# ProPrj_My_FOC_DRV8313_Share.net
KiCad netlist of a schematic drawn in EasyEDA Pro
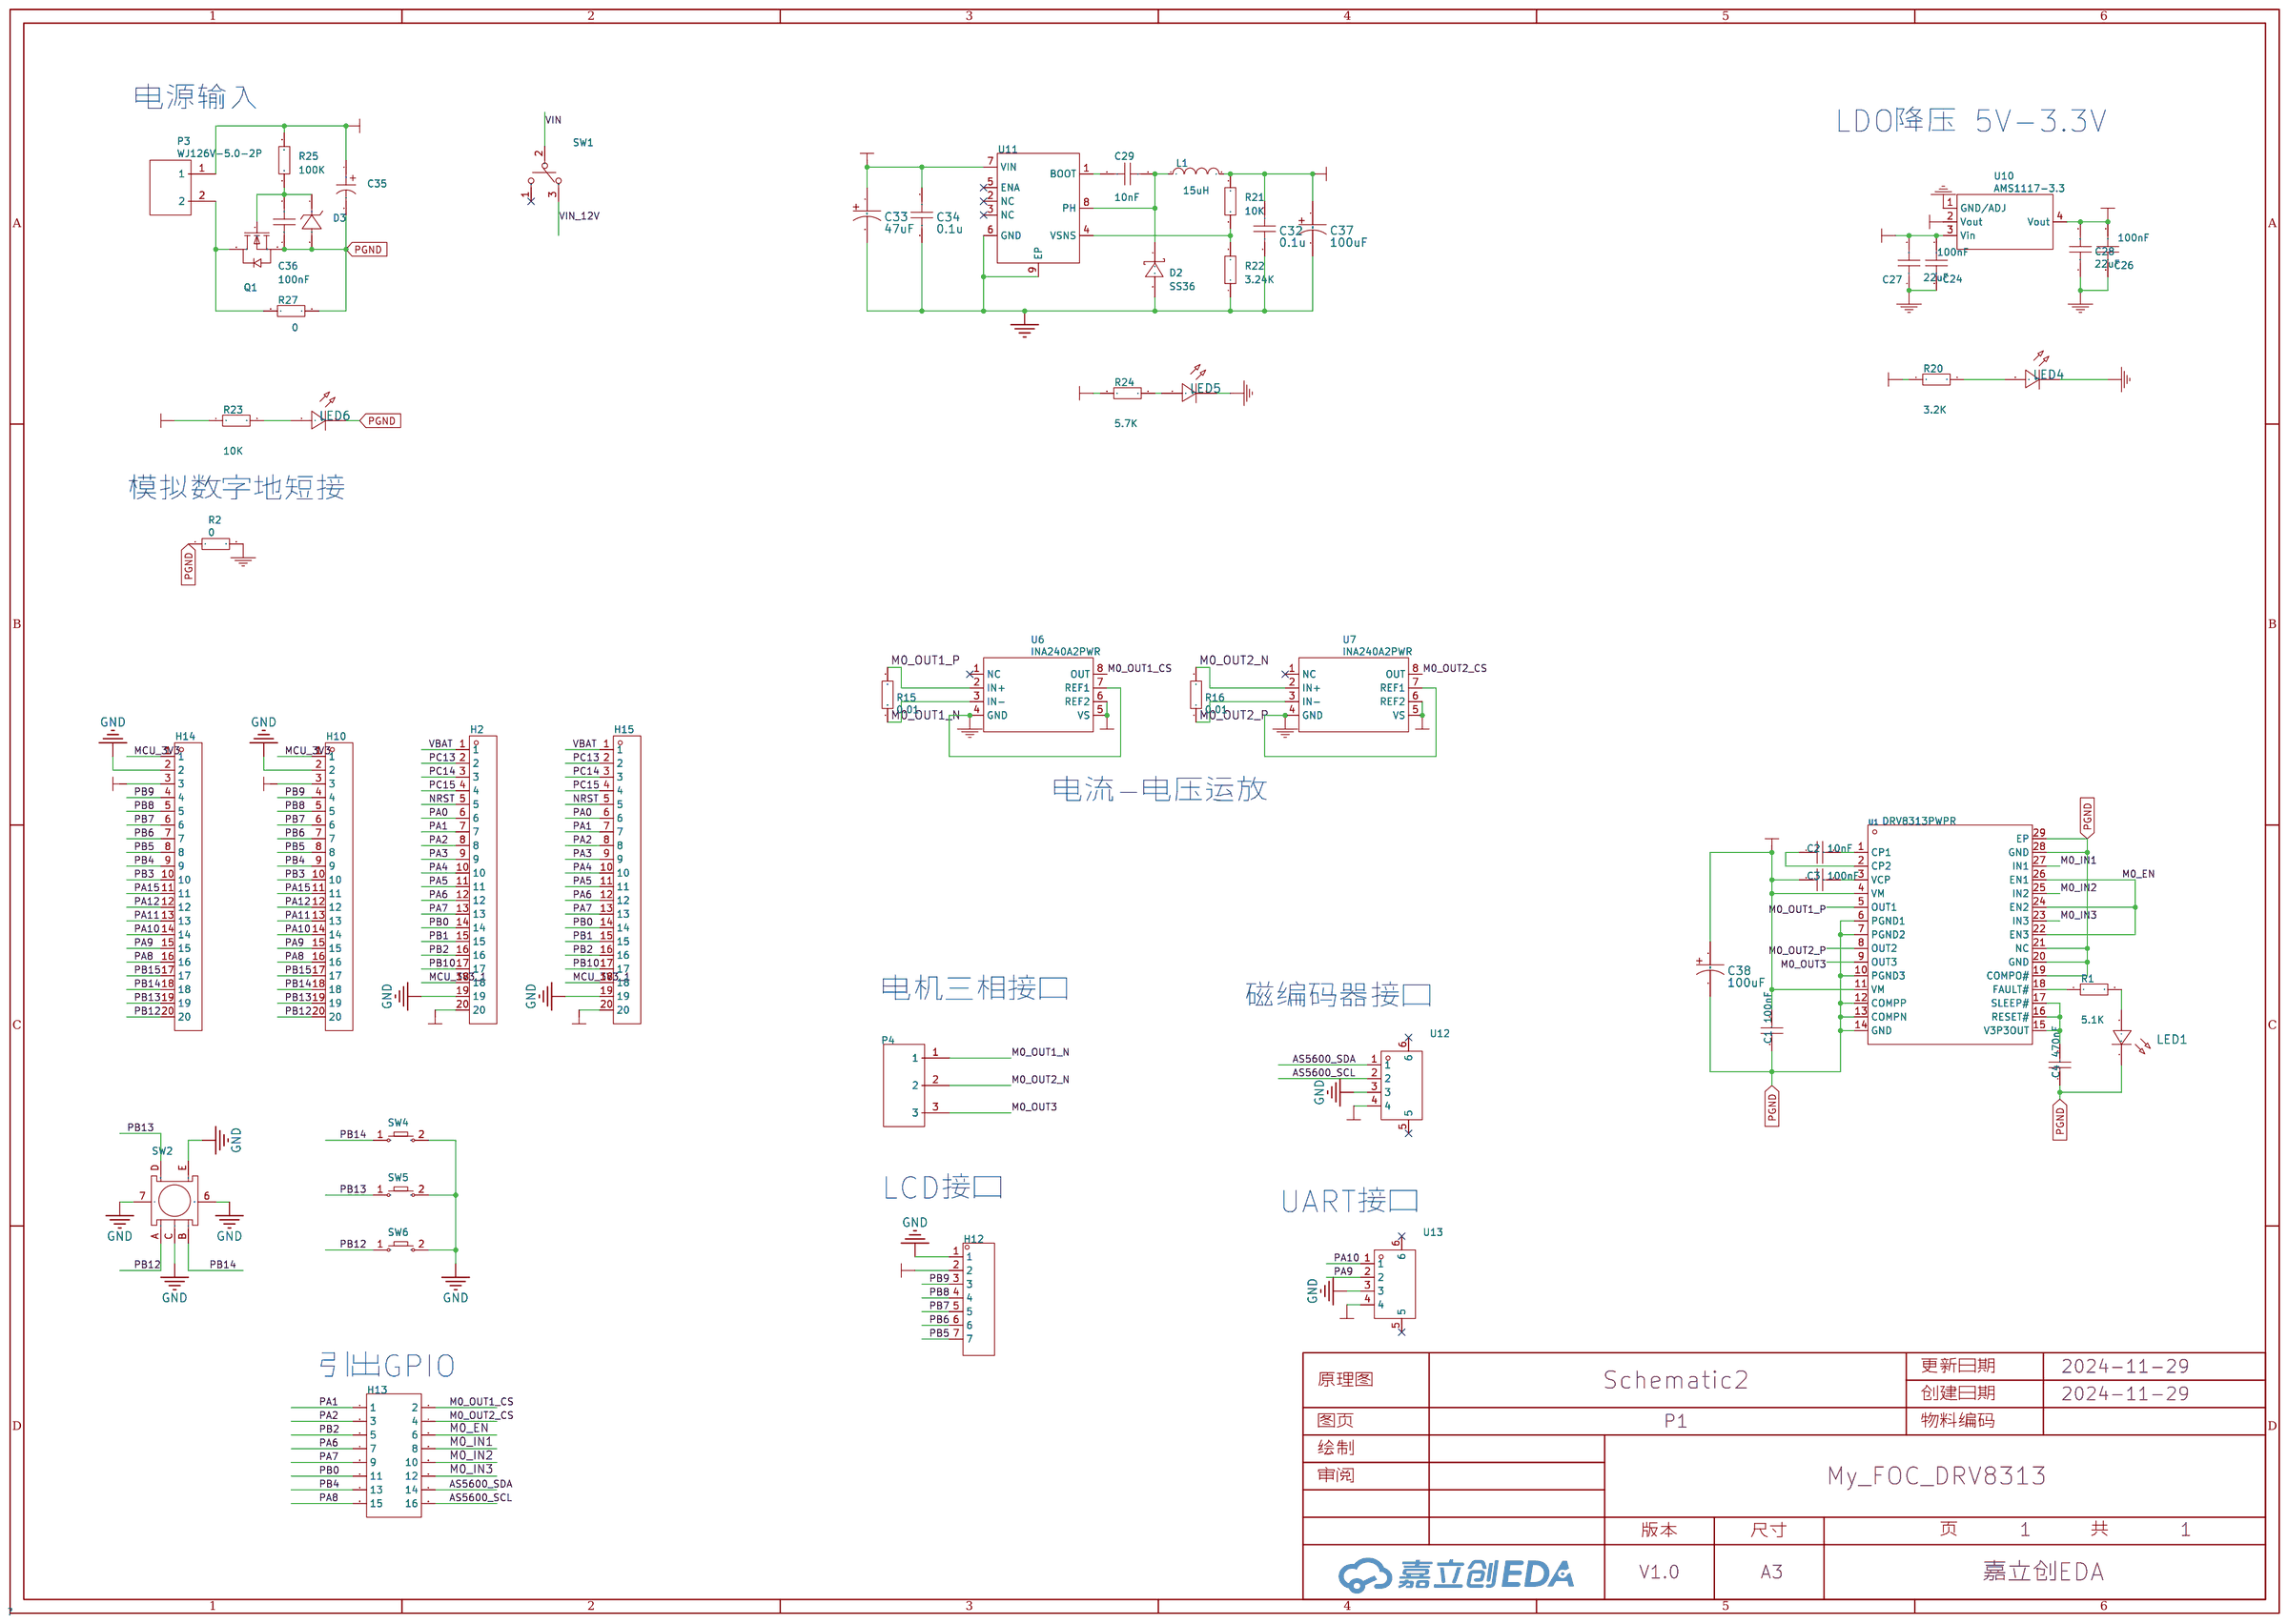
[diagram p0: schematic sheet]

(export (version "E")
  (design (tool "Eeschema 10.0.6"))
  (components
    (comp (ref "C1")
      (value "100nF")
      (footprint "easyedapro:C0603")
      (description "容值:100nF;精度:±10%;额定电压:50V;材质(温度系数):X7R;")
      (fields (field (name "Manufacturer Part") "0603B104K500NT") (field (name "Manufacturer") "FH(风华)"))
      (libsource (lib "easyedapro") (part "0603B104K500NT"))
    )
    (comp (ref "C2")
      (value "10nF")
      (footprint "easyedapro:C0603")
      (description "容值:10nF;精度:±10%;额定电压:50V;材质(温度系数):X7R;")
      (fields
        (field (name "Manufacturer Part") "CC0603KRX7R9BB103")
        (field (name "Manufacturer") "YAGEO(国巨)")
      )
      (libsource (lib "easyedapro") (part "CC0603KRX7R9BB103"))
    )
    (comp (ref "C3")
      (value "100nF")
      (footprint "easyedapro:C0603")
      (description "容值:100nF;精度:±10%;额定电压:50V;材质(温度系数):X7R;")
      (fields (field (name "Manufacturer Part") "0603B104K500NT") (field (name "Manufacturer") "FH(风华)"))
      (libsource (lib "easyedapro") (part "0603B104K500NT"))
    )
    (comp (ref "C4")
      (value "470nF")
      (footprint "easyedapro:C0603")
      (description "容值:470nF;精度:±10%;额定电压:25V;材质(温度系数):X7R;")
      (fields
        (field (name "Manufacturer Part") "CL10B474KA8NNNC")
        (field (name "Manufacturer") "SAMSUNG(三星)")
      )
      (libsource (lib "easyedapro") (part "CL10B474KA8NNNC"))
    )
    (comp (ref "C24")
      (value "100nF")
      (footprint "easyedapro:C0603")
      (fields (field (name "Manufacturer Part") "CC0603KRX7R9BB104") (field (name "Manufacturer") "YAGEO"))
      (libsource (lib "easyedapro") (part "100nF"))
    )
    (comp (ref "C26")
      (value "100nF")
      (footprint "easyedapro:C0603")
      (fields (field (name "Manufacturer Part") "CC0603KRX7R9BB104") (field (name "Manufacturer") "YAGEO"))
      (libsource (lib "easyedapro") (part "100nF"))
    )
    (comp (ref "C27")
      (value "22uF")
      (footprint "easyedapro:C0603")
      (fields (field (name "Manufacturer Part") "CL10A226MQ8NRNC") (field (name "Manufacturer") "SAMSUNG"))
      (libsource (lib "") (part "22uF_1"))
    )
    (comp (ref "C28")
      (value "22uF")
      (footprint "easyedapro:C0603")
      (fields (field (name "Manufacturer Part") "CL10A226MQ8NRNC") (field (name "Manufacturer") "SAMSUNG"))
      (libsource (lib "") (part "22uF_1"))
    )
    (comp (ref "C29")
      (value "10nF")
      (footprint "easyedapro:C0603")
      (libsource (lib "easyedapro") (part "CapAcitance"))
    )
    (comp (ref "C32")
      (value "0.1u")
      (footprint "easyedapro:C0603")
      (libsource (lib "easyedapro") (part "0.1u"))
    )
    (comp (ref "C33")
      (value "47uF")
      (footprint "easyedapro:CAP-SMD_BD5.0-L5.3-W5.3-FD")
      (fields (field (name "Manufacturer Part") "RVE1E220M0505") (field (name "Manufacturer") "HONOR"))
      (libsource (lib "easyedapro") (part "22uF"))
    )
    (comp (ref "C34")
      (value "0.1u")
      (footprint "easyedapro:C0603")
      (libsource (lib "easyedapro") (part "0.1u"))
    )
    (comp (ref "C35")
      (value "LZ1C471M0810")
      (footprint "easyedapro:CAP-SMD_BD8.0-L8.3-W8.3-LS9.3-FD-2")
      (description "容值: 470uF 精度: ±20% 额定电压: 16V 电容直径: 8mm 电容高度: 10.5mm 工作温度: 2000H@105°C贴片型铝电解电容")
      (fields (field (name "Manufacturer") "JARSON(伽盛)"))
      (libsource (lib "easyedapro") (part "LZ1C471M0810"))
    )
    (comp (ref "C36")
      (value "100nF")
      (footprint "easyedapro:C0603")
      (libsource (lib "easyedapro") (part "CapAcitance"))
    )
    (comp (ref "C37")
      (value "100uF")
      (footprint "easyedapro:CAP-SMD_BD5.0-L5.3-W5.3-FD")
      (fields (field (name "Manufacturer Part") "RVE1E220M0505") (field (name "Manufacturer") "HONOR"))
      (libsource (lib "easyedapro") (part "22uF"))
    )
    (comp (ref "C38")
      (value "100uF")
      (footprint "easyedapro:CAP-SMD_BD5.0-L5.3-W5.3-FD")
      (fields (field (name "Manufacturer Part") "RVE1E220M0505") (field (name "Manufacturer") "HONOR"))
      (libsource (lib "easyedapro") (part "22uF"))
    )
    (comp (ref "D2")
      (value "SS36")
      (footprint "easyedapro:SMA_L4.3-W2.6-LS5.2-RD")
      (fields (field (name "Manufacturer") "MDD"))
      (libsource (lib "easyedapro") (part "SS36"))
    )
    (comp (ref "D3")
      (value "ZMM12")
      (footprint "easyedapro:LL-34_L3.5-W1.5-RD")
      (description "稳压值(标称值):-;功率(Pd):500mW;")
      (fields (field (name "Manufacturer") "Slkor(萨科微)"))
      (libsource (lib "easyedapro") (part "ZMM12_C707203"))
    )
    (comp (ref "H2")
      (value "~")
      (footprint "easyedapro:HDR-TH_20P-P2.54-V-M-1")
      (libsource (lib "easyedapro") (part "HDR_2.54-1x20P"))
    )
    (comp (ref "H10")
      (value "~")
      (footprint "easyedapro:HDR-TH_20P-P2.54-V-M-1")
      (libsource (lib "easyedapro") (part "HDR_2.54-1x20P"))
    )
    (comp (ref "H12")
      (value "~")
      (footprint "easyedapro:HDR-TH_7P-P2.54-V-F")
      (libsource (lib "easyedapro") (part "220S-1*7P H=8.5MM Ytype Gold-plated"))
    )
    (comp (ref "H13")
      (value "~")
      (footprint "easyedapro:HDR-TH_16P-P2.54-V-F-R2-C8-S2.54-1")
      (libsource (lib "easyedapro") (part "HDR-F-2.54_2x8"))
    )
    (comp (ref "H14")
      (value "~")
      (footprint "easyedapro:HDR-TH_20P-P2.54-V-M-1")
      (libsource (lib "easyedapro") (part "HDR_2.54-1x20P"))
    )
    (comp (ref "H15")
      (value "~")
      (footprint "easyedapro:HDR-TH_20P-P2.54-V-M-1")
      (libsource (lib "easyedapro") (part "HDR_2.54-1x20P"))
    )
    (comp (ref "L1")
      (value "15uH")
      (footprint "easyedapro:IND-SMD_L4.0-W4.0")
      (description "电感值:10uH;精度:±20%;额定电流:840mA;饱和电流(Isat):1.6A;类型:-;")
      (fields (field (name "Manufacturer Part") "SWPA4018S100MT") (field (name "Manufacturer") "Sunlord(顺络)"))
      (libsource (lib "easyedapro") (part "SWPA4018S100MT"))
    )
    (comp (ref "LED1")
      (value "~")
      (footprint "easyedapro:LED_0603")
      (libsource (lib "easyedapro") (part "LED_R"))
    )
    (comp (ref "LED4")
      (value "~")
      (footprint "easyedapro:LED_0603")
      (libsource (lib "easyedapro") (part "LED_R"))
    )
    (comp (ref "LED5")
      (value "~")
      (footprint "easyedapro:LED_0603")
      (libsource (lib "easyedapro") (part "LED_R"))
    )
    (comp (ref "LED6")
      (value "~")
      (footprint "easyedapro:LED_0603")
      (libsource (lib "easyedapro") (part "LED_R"))
    )
    (comp (ref "P3")
      (value "WJ126V-5.0-2P")
      (footprint "easyedapro:conn-th_wj126v-5.0-2p")
      (fields (field (name "Manufacturer") "ReliaPro"))
      (libsource (lib "easyedapro") (part "WJ126V-5.0-2P"))
    )
    (comp (ref "P4")
      (value "WJ126V-5.0-3P")
      (footprint "easyedapro:CONN-TH_3P-P5.00_WJ126V-5.0-3P")
      (fields (field (name "Manufacturer") "KANGNEX(康奈克斯电气)"))
      (libsource (lib "easyedapro") (part "WJ126V-5.0-3P"))
    )
    (comp (ref "Q1")
      (value "AO3400A")
      (footprint "easyedapro:SOT-23-3_L2.9-W1.3-P1.90-LS2.4-BR")
      (fields (field (name "Manufacturer") "UMW(友台半导体)"))
      (libsource (lib "easyedapro") (part "AO3400A_C347475"))
    )
    (comp (ref "R1") (value "5.1K") (footprint "easyedapro:R0603") (libsource (lib "easyedapro") (part "电阻")))
    (comp (ref "R2")
      (value "0")
      (footprint "easyedapro:R0805")
      (fields (field (name "Manufacturer Part") "RM10FTN0") (field (name "Manufacturer") "TA-I Tech"))
      (libsource (lib "easyedapro") (part "0"))
    )
    (comp (ref "R15")
      (value "0.01")
      (footprint "easyedapro:R1206")
      (fields (field (name "Manufacturer Part") "RTT06R010FTP") (field (name "Manufacturer") "RALEC"))
      (libsource (lib "easyedapro") (part "0.01"))
    )
    (comp (ref "R16")
      (value "0.01")
      (footprint "easyedapro:R1206")
      (fields (field (name "Manufacturer Part") "RTT06R010FTP") (field (name "Manufacturer") "RALEC"))
      (libsource (lib "easyedapro") (part "0.01"))
    )
    (comp (ref "R20")
      (value "3.2K")
      (footprint "easyedapro:R0603")
      (libsource (lib "easyedapro") (part "电阻"))
    )
    (comp (ref "R21") (value "10K") (footprint "easyedapro:R0603") (libsource (lib "easyedapro") (part "电阻")))
    (comp (ref "R22")
      (value "3.24K")
      (footprint "easyedapro:R0603")
      (libsource (lib "easyedapro") (part "电阻"))
    )
    (comp (ref "R23") (value "10K") (footprint "easyedapro:R0603") (libsource (lib "easyedapro") (part "电阻")))
    (comp (ref "R24")
      (value "5.7K")
      (footprint "easyedapro:R0603")
      (libsource (lib "easyedapro") (part "电阻"))
    )
    (comp (ref "R25")
      (value "100K")
      (footprint "easyedapro:R0603")
      (libsource (lib "easyedapro") (part "电阻"))
    )
    (comp (ref "R27") (value "0") (footprint "easyedapro:R0603") (libsource (lib "easyedapro") (part "电阻")))
    (comp (ref "SW1")
      (value "MT-0-103-A101-M200-RS")
      (footprint "easyedapro:SW-TH_MT-0-103-A101-M200-RS")
      (description "电路结构:单刀双掷;机械寿命:-;额定电流:5A;额定电压(AC):125V;安装方式:直插;")
      (fields (field (name "Manufacturer") "YUEN FUNG(源丰)"))
      (libsource (lib "easyedapro") (part "MT-0-103-A101-M200-RS+PJ"))
    )
    (comp (ref "SW2")
      (value "EC11E15244G1")
      (footprint "easyedapro:SW-TH_EC11E15244G1")
      (fields (field (name "Manufacturer") "ALPSALPINE(阿尔卑斯阿尔派)"))
      (libsource (lib "easyedapro") (part "EC11E15244G1"))
    )
    (comp (ref "SW4")
      (value "~")
      (footprint "easyedapro:Key_SMD_3.6x6.1x2.5")
      (libsource (lib "easyedapro") (part "轻触按键x2"))
    )
    (comp (ref "SW5")
      (value "~")
      (footprint "easyedapro:Key_SMD_3.6x6.1x2.5")
      (libsource (lib "easyedapro") (part "轻触按键x2"))
    )
    (comp (ref "SW6")
      (value "~")
      (footprint "easyedapro:Key_SMD_3.6x6.1x2.5")
      (libsource (lib "easyedapro") (part "轻触按键x2"))
    )
    (comp (ref "U1")
      (value "DRV8313PWPR")
      (footprint "easyedapro:HTSSOP-28_L9.8-W4.5-P0.65-LS6.6-BL-EP")
      (description "驱动电机类型:无刷直流BLDC;电源电压:8V~60V;输出电流:-;接口:并行;")
      (fields (field (name "Manufacturer") "TI(德州仪器)"))
      (libsource (lib "easyedapro") (part "DRV8313PWPR"))
    )
    (comp (ref "U6")
      (value "INA240A2PWR")
      (footprint "easyedapro:TSSOP-8_L4.4-W3.0-P0.65-LS6.4-BL")
      (fields (field (name "Manufacturer") "TI"))
      (libsource (lib "easyedapro") (part "INA240A2PWR"))
    )
    (comp (ref "U7")
      (value "INA240A2PWR")
      (footprint "easyedapro:TSSOP-8_L4.4-W3.0-P0.65-LS6.4-BL")
      (fields (field (name "Manufacturer") "TI"))
      (libsource (lib "easyedapro") (part "INA240A2PWR"))
    )
    (comp (ref "U10")
      (value "AMS1117-3.3")
      (footprint "easyedapro:SOT-223-3_L6.5-W3.4-P2.30-LS7.0-BR")
      (fields (field (name "Manufacturer") "AMS"))
      (libsource (lib "easyedapro") (part "AMS1117-3.3"))
    )
    (comp (ref "U11")
      (value "TPS5430DDA")
      (footprint "easyedapro:ESOP-8_L4.9-W3.9-P1.27-LS6.0-BL-EP-2")
      (description "功能类型:降压型;输出类型:可调;输入电压:5.5V~36V;输出电压:1.221V~32.04V;输出电流(最大值):3A;")
      (fields (field (name "Manufacturer") "TI(德州仪器)"))
      (libsource (lib "easyedapro") (part "TPS5430DDA"))
    )
    (comp (ref "U12")
      (value "XY-PH2.0-4A61")
      (footprint "easyedapro:CONN-SMD_4P-P2.00_XYECONN_XY-PH2.0-4A61")
      (description "插针结构:1x4P;间距:2mm;安装方式:卧贴;总PIN数:4P;排数:1;每排PIN数:4;")
      (fields (field (name "Manufacturer") "XYECONN(辛译)"))
      (libsource (lib "easyedapro") (part "XY-PH2.0-4A61"))
    )
    (comp (ref "U13")
      (value "XY-PH2.0-4A61")
      (footprint "easyedapro:CONN-SMD_4P-P2.00_XYECONN_XY-PH2.0-4A61")
      (description "插针结构:1x4P;间距:2mm;安装方式:卧贴;总PIN数:4P;排数:1;每排PIN数:4;")
      (fields (field (name "Manufacturer") "XYECONN(辛译)"))
      (libsource (lib "easyedapro") (part "XY-PH2.0-4A61"))
    )
  )
  (nets
    (net (code "1") (name "/AS5600_SCL") (class "Default")
      (node (ref "H13") (pin "16") (pinfunction "16_16") (pintype "input"))
      (node (ref "U12") (pin "2") (pinfunction "2_2") (pintype "unspecified"))
    )
    (net (code "2") (name "/AS5600_SDA") (class "Default")
      (node (ref "H13") (pin "14") (pinfunction "14_14") (pintype "input"))
      (node (ref "U12") (pin "1") (pinfunction "1_1") (pintype "unspecified"))
    )
    (net (code "3") (name "/M0_EN") (class "Default")
      (node (ref "H13") (pin "6") (pinfunction "6_6") (pintype "input"))
      (node (ref "U1") (pin "22") (pinfunction "EN3_22") (pintype "input"))
      (node (ref "U1") (pin "24") (pinfunction "EN2_24") (pintype "input"))
      (node (ref "U1") (pin "26") (pinfunction "EN1_26") (pintype "input"))
    )
    (net (code "4") (name "/M0_IN1") (class "Default")
      (node (ref "H13") (pin "8") (pinfunction "8_8") (pintype "input"))
      (node (ref "U1") (pin "27") (pinfunction "IN1_27") (pintype "input"))
    )
    (net (code "5") (name "/M0_IN2") (class "Default")
      (node (ref "H13") (pin "10") (pinfunction "10_10") (pintype "input"))
      (node (ref "U1") (pin "25") (pinfunction "IN2_25") (pintype "input"))
    )
    (net (code "6") (name "/M0_IN3") (class "Default")
      (node (ref "H13") (pin "12") (pinfunction "12_12") (pintype "input"))
      (node (ref "U1") (pin "23") (pinfunction "IN3_23") (pintype "input"))
    )
    (net (code "7") (name "/M0_OUT1_CS") (class "Default")
      (node (ref "H13") (pin "2") (pinfunction "2_2") (pintype "input"))
      (node (ref "U6") (pin "8") (pinfunction "OUT_8") (pintype "unspecified"))
    )
    (net (code "8") (name "/M0_OUT1_N") (class "Default")
      (node (ref "P4") (pin "1") (pinfunction "1_1") (pintype "input"))
      (node (ref "R15") (pin "1") (pinfunction "1_1") (pintype "unspecified"))
      (node (ref "U6") (pin "3") (pinfunction "IN-_3") (pintype "unspecified"))
    )
    (net (code "9") (name "/M0_OUT1_P") (class "Default")
      (node (ref "R15") (pin "2") (pinfunction "2_2") (pintype "unspecified"))
      (node (ref "U1") (pin "5") (pinfunction "OUT1_5") (pintype "input"))
      (node (ref "U6") (pin "2") (pinfunction "IN+_2") (pintype "unspecified"))
    )
    (net (code "10") (name "/M0_OUT2_CS") (class "Default")
      (node (ref "H13") (pin "4") (pinfunction "4_4") (pintype "input"))
      (node (ref "U7") (pin "8") (pinfunction "OUT_8") (pintype "unspecified"))
    )
    (net (code "11") (name "/M0_OUT2_N") (class "Default")
      (node (ref "P4") (pin "2") (pinfunction "2_2") (pintype "input"))
      (node (ref "R16") (pin "2") (pinfunction "2_2") (pintype "unspecified"))
      (node (ref "U7") (pin "2") (pinfunction "IN+_2") (pintype "unspecified"))
    )
    (net (code "12") (name "/M0_OUT2_P") (class "Default")
      (node (ref "R16") (pin "1") (pinfunction "1_1") (pintype "unspecified"))
      (node (ref "U1") (pin "8") (pinfunction "OUT2_8") (pintype "input"))
      (node (ref "U7") (pin "3") (pinfunction "IN-_3") (pintype "unspecified"))
    )
    (net (code "13") (name "/M0_OUT3") (class "Default")
      (node (ref "P4") (pin "3") (pinfunction "3_3") (pintype "input"))
      (node (ref "U1") (pin "9") (pinfunction "OUT3_9") (pintype "input"))
    )
    (net (code "14") (name "/MCU_3V3") (class "Default")
      (node (ref "H10") (pin "1") (pinfunction "1_1") (pintype "input"))
      (node (ref "H14") (pin "1") (pinfunction "1_1") (pintype "input"))
    )
    (net (code "15") (name "/MCU_3V3_1") (class "Default")
      (node (ref "H15") (pin "18") (pinfunction "18_18") (pintype "input"))
      (node (ref "H2") (pin "18") (pinfunction "18_18") (pintype "input"))
    )
    (net (code "16") (name "/NRST") (class "Default")
      (node (ref "H15") (pin "5") (pinfunction "5_5") (pintype "input"))
      (node (ref "H2") (pin "5") (pinfunction "5_5") (pintype "input"))
    )
    (net (code "17") (name "/PA0") (class "Default")
      (node (ref "H15") (pin "6") (pinfunction "6_6") (pintype "input"))
      (node (ref "H2") (pin "6") (pinfunction "6_6") (pintype "input"))
    )
    (net (code "18") (name "/PA1") (class "Default")
      (node (ref "H13") (pin "1") (pinfunction "1_1") (pintype "input"))
      (node (ref "H15") (pin "7") (pinfunction "7_7") (pintype "input"))
      (node (ref "H2") (pin "7") (pinfunction "7_7") (pintype "input"))
    )
    (net (code "19") (name "/PA2") (class "Default")
      (node (ref "H13") (pin "3") (pinfunction "3_3") (pintype "input"))
      (node (ref "H15") (pin "8") (pinfunction "8_8") (pintype "input"))
      (node (ref "H2") (pin "8") (pinfunction "8_8") (pintype "input"))
    )
    (net (code "20") (name "/PA3") (class "Default")
      (node (ref "H15") (pin "9") (pinfunction "9_9") (pintype "input"))
      (node (ref "H2") (pin "9") (pinfunction "9_9") (pintype "input"))
    )
    (net (code "21") (name "/PA4") (class "Default")
      (node (ref "H15") (pin "10") (pinfunction "10_10") (pintype "input"))
      (node (ref "H2") (pin "10") (pinfunction "10_10") (pintype "input"))
    )
    (net (code "22") (name "/PA5") (class "Default")
      (node (ref "H15") (pin "11") (pinfunction "11_11") (pintype "input"))
      (node (ref "H2") (pin "11") (pinfunction "11_11") (pintype "input"))
    )
    (net (code "23") (name "/PA6") (class "Default")
      (node (ref "H13") (pin "7") (pinfunction "7_7") (pintype "input"))
      (node (ref "H15") (pin "12") (pinfunction "12_12") (pintype "input"))
      (node (ref "H2") (pin "12") (pinfunction "12_12") (pintype "input"))
    )
    (net (code "24") (name "/PA7") (class "Default")
      (node (ref "H13") (pin "9") (pinfunction "9_9") (pintype "input"))
      (node (ref "H15") (pin "13") (pinfunction "13_13") (pintype "input"))
      (node (ref "H2") (pin "13") (pinfunction "13_13") (pintype "input"))
    )
    (net (code "25") (name "/PA8") (class "Default")
      (node (ref "H10") (pin "16") (pinfunction "16_16") (pintype "input"))
      (node (ref "H13") (pin "15") (pinfunction "15_15") (pintype "input"))
      (node (ref "H14") (pin "16") (pinfunction "16_16") (pintype "input"))
    )
    (net (code "26") (name "/PA9") (class "Default")
      (node (ref "H10") (pin "15") (pinfunction "15_15") (pintype "input"))
      (node (ref "H14") (pin "15") (pinfunction "15_15") (pintype "input"))
      (node (ref "U13") (pin "2") (pinfunction "2_2") (pintype "unspecified"))
    )
    (net (code "27") (name "/PA10") (class "Default")
      (node (ref "H10") (pin "14") (pinfunction "14_14") (pintype "input"))
      (node (ref "H14") (pin "14") (pinfunction "14_14") (pintype "input"))
      (node (ref "U13") (pin "1") (pinfunction "1_1") (pintype "unspecified"))
    )
    (net (code "28") (name "/PA11") (class "Default")
      (node (ref "H10") (pin "13") (pinfunction "13_13") (pintype "input"))
      (node (ref "H14") (pin "13") (pinfunction "13_13") (pintype "input"))
    )
    (net (code "29") (name "/PA12") (class "Default")
      (node (ref "H10") (pin "12") (pinfunction "12_12") (pintype "input"))
      (node (ref "H14") (pin "12") (pinfunction "12_12") (pintype "input"))
    )
    (net (code "30") (name "/PA15") (class "Default")
      (node (ref "H10") (pin "11") (pinfunction "11_11") (pintype "input"))
      (node (ref "H14") (pin "11") (pinfunction "11_11") (pintype "input"))
    )
    (net (code "31") (name "/PB0") (class "Default")
      (node (ref "H13") (pin "11") (pinfunction "11_11") (pintype "input"))
      (node (ref "H15") (pin "14") (pinfunction "14_14") (pintype "input"))
      (node (ref "H2") (pin "14") (pinfunction "14_14") (pintype "input"))
    )
    (net (code "32") (name "/PB1") (class "Default")
      (node (ref "H15") (pin "15") (pinfunction "15_15") (pintype "input"))
      (node (ref "H2") (pin "15") (pinfunction "15_15") (pintype "input"))
    )
    (net (code "33") (name "/PB2") (class "Default")
      (node (ref "H13") (pin "5") (pinfunction "5_5") (pintype "input"))
      (node (ref "H15") (pin "16") (pinfunction "16_16") (pintype "input"))
      (node (ref "H2") (pin "16") (pinfunction "16_16") (pintype "input"))
    )
    (net (code "34") (name "/PB3") (class "Default")
      (node (ref "H10") (pin "10") (pinfunction "10_10") (pintype "input"))
      (node (ref "H14") (pin "10") (pinfunction "10_10") (pintype "input"))
    )
    (net (code "35") (name "/PB4") (class "Default")
      (node (ref "H10") (pin "9") (pinfunction "9_9") (pintype "input"))
      (node (ref "H13") (pin "13") (pinfunction "13_13") (pintype "input"))
      (node (ref "H14") (pin "9") (pinfunction "9_9") (pintype "input"))
    )
    (net (code "36") (name "/PB5") (class "Default")
      (node (ref "H10") (pin "8") (pinfunction "8_8") (pintype "input"))
      (node (ref "H12") (pin "7") (pinfunction "7_7") (pintype "unspecified"))
      (node (ref "H14") (pin "8") (pinfunction "8_8") (pintype "input"))
    )
    (net (code "37") (name "/PB6") (class "Default")
      (node (ref "H10") (pin "7") (pinfunction "7_7") (pintype "input"))
      (node (ref "H12") (pin "6") (pinfunction "6_6") (pintype "unspecified"))
      (node (ref "H14") (pin "7") (pinfunction "7_7") (pintype "input"))
    )
    (net (code "38") (name "/PB7") (class "Default")
      (node (ref "H10") (pin "6") (pinfunction "6_6") (pintype "input"))
      (node (ref "H12") (pin "5") (pinfunction "5_5") (pintype "unspecified"))
      (node (ref "H14") (pin "6") (pinfunction "6_6") (pintype "input"))
    )
    (net (code "39") (name "/PB8") (class "Default")
      (node (ref "H10") (pin "5") (pinfunction "5_5") (pintype "input"))
      (node (ref "H12") (pin "4") (pinfunction "4_4") (pintype "unspecified"))
      (node (ref "H14") (pin "5") (pinfunction "5_5") (pintype "input"))
    )
    (net (code "40") (name "/PB9") (class "Default")
      (node (ref "H10") (pin "4") (pinfunction "4_4") (pintype "input"))
      (node (ref "H12") (pin "3") (pinfunction "3_3") (pintype "unspecified"))
      (node (ref "H14") (pin "4") (pinfunction "4_4") (pintype "input"))
    )
    (net (code "41") (name "/PB10") (class "Default")
      (node (ref "H15") (pin "17") (pinfunction "17_17") (pintype "input"))
      (node (ref "H2") (pin "17") (pinfunction "17_17") (pintype "input"))
    )
    (net (code "42") (name "/PB12") (class "Default")
      (node (ref "H10") (pin "20") (pinfunction "20_20") (pintype "input"))
      (node (ref "H14") (pin "20") (pinfunction "20_20") (pintype "input"))
      (node (ref "SW2") (pin "A") (pinfunction "A_A") (pintype "input"))
      (node (ref "SW6") (pin "1") (pinfunction "1_1") (pintype "input"))
    )
    (net (code "43") (name "/PB13") (class "Default")
      (node (ref "H10") (pin "19") (pinfunction "19_19") (pintype "input"))
      (node (ref "H14") (pin "19") (pinfunction "19_19") (pintype "input"))
      (node (ref "SW2") (pin "D") (pinfunction "D_D") (pintype "input"))
      (node (ref "SW5") (pin "1") (pinfunction "1_1") (pintype "input"))
    )
    (net (code "44") (name "/PB14") (class "Default")
      (node (ref "H10") (pin "18") (pinfunction "18_18") (pintype "input"))
      (node (ref "H14") (pin "18") (pinfunction "18_18") (pintype "input"))
      (node (ref "SW2") (pin "B") (pinfunction "B_B") (pintype "input"))
      (node (ref "SW4") (pin "1") (pinfunction "1_1") (pintype "input"))
    )
    (net (code "45") (name "/PB15") (class "Default")
      (node (ref "H10") (pin "17") (pinfunction "17_17") (pintype "input"))
      (node (ref "H14") (pin "17") (pinfunction "17_17") (pintype "input"))
    )
    (net (code "46") (name "/PC13") (class "Default")
      (node (ref "H15") (pin "2") (pinfunction "2_2") (pintype "input"))
      (node (ref "H2") (pin "2") (pinfunction "2_2") (pintype "input"))
    )
    (net (code "47") (name "/PC14") (class "Default")
      (node (ref "H15") (pin "3") (pinfunction "3_3") (pintype "input"))
      (node (ref "H2") (pin "3") (pinfunction "3_3") (pintype "input"))
    )
    (net (code "48") (name "/PC15") (class "Default")
      (node (ref "H15") (pin "4") (pinfunction "4_4") (pintype "input"))
      (node (ref "H2") (pin "4") (pinfunction "4_4") (pintype "input"))
    )
    (net (code "49") (name "/VBAT") (class "Default")
      (node (ref "H15") (pin "1") (pinfunction "1_1") (pintype "input"))
      (node (ref "H2") (pin "1") (pinfunction "1_1") (pintype "input"))
    )
    (net (code "50") (name "GND") (class "Default")
      (node (ref "C24") (pin "2") (pinfunction "2_2") (pintype "unspecified"))
      (node (ref "C26") (pin "2") (pinfunction "2_2") (pintype "unspecified"))
      (node (ref "C27") (pin "1") (pinfunction "1_1") (pintype "unspecified"))
      (node (ref "C28") (pin "1") (pinfunction "1_1") (pintype "unspecified"))
      (node (ref "C32") (pin "2") (pinfunction "2_2") (pintype "input"))
      (node (ref "C33") (pin "2") (pinfunction "2_2") (pintype "input"))
      (node (ref "C34") (pin "2") (pinfunction "2_2") (pintype "input"))
      (node (ref "C37") (pin "2") (pinfunction "2_2") (pintype "input"))
      (node (ref "D2") (pin "2") (pinfunction "A_2") (pintype "unspecified"))
      (node (ref "H10") (pin "2") (pinfunction "2_2") (pintype "input"))
      (node (ref "H12") (pin "1") (pinfunction "1_1") (pintype "unspecified"))
      (node (ref "H14") (pin "2") (pinfunction "2_2") (pintype "input"))
      (node (ref "H15") (pin "19") (pinfunction "19_19") (pintype "input"))
      (node (ref "H2") (pin "19") (pinfunction "19_19") (pintype "input"))
      (node (ref "LED4") (pin "1") (pinfunction "C_1") (pintype "input"))
      (node (ref "LED5") (pin "1") (pinfunction "C_1") (pintype "input"))
      (node (ref "R2") (pin "2") (pinfunction "2_2") (pintype "unspecified"))
      (node (ref "R22") (pin "1") (pinfunction "1_1") (pintype "input"))
      (node (ref "SW2") (pin "6") (pinfunction "6_6") (pintype "input"))
      (node (ref "SW2") (pin "7") (pinfunction "7_7") (pintype "input"))
      (node (ref "SW2") (pin "C") (pinfunction "C_C") (pintype "input"))
      (node (ref "SW2") (pin "E") (pinfunction "E_E") (pintype "input"))
      (node (ref "SW4") (pin "2") (pinfunction "2_2") (pintype "input"))
      (node (ref "SW5") (pin "2") (pinfunction "2_2") (pintype "input"))
      (node (ref "SW6") (pin "2") (pinfunction "2_2") (pintype "input"))
      (node (ref "U10") (pin "1") (pinfunction "GND/ADJ_1") (pintype "unspecified"))
      (node (ref "U11") (pin "6") (pinfunction "GND_6") (pintype "unspecified"))
      (node (ref "U11") (pin "9") (pinfunction "EP_9") (pintype "unspecified"))
      (node (ref "U12") (pin "3") (pinfunction "3_3") (pintype "unspecified"))
      (node (ref "U13") (pin "3") (pinfunction "3_3") (pintype "unspecified"))
      (node (ref "U6") (pin "4") (pinfunction "GND_4") (pintype "unspecified"))
      (node (ref "U6") (pin "7") (pinfunction "REF1_7") (pintype "unspecified"))
      (node (ref "U7") (pin "4") (pinfunction "GND_4") (pintype "unspecified"))
      (node (ref "U7") (pin "7") (pinfunction "REF1_7") (pintype "unspecified"))
    )
    (net (code "51") (name "MCU_5V") (class "Default")
      (node (ref "H15") (pin "20") (pinfunction "20_20") (pintype "input"))
      (node (ref "H2") (pin "20") (pinfunction "20_20") (pintype "input"))
    )
    (net (code "52") (name "Net-(D2-K)") (class "Default")
      (node (ref "C29") (pin "2") (pinfunction "2_2") (pintype "input"))
      (node (ref "D2") (pin "1") (pinfunction "K_1") (pintype "unspecified"))
      (node (ref "L1") (pin "1") (pinfunction "1_1") (pintype "unspecified"))
      (node (ref "U11") (pin "8") (pinfunction "PH_8") (pintype "unspecified"))
    )
    (net (code "53") (name "Net-(D3-K)") (class "Default")
      (node (ref "C36") (pin "2") (pinfunction "2_2") (pintype "input"))
      (node (ref "D3") (pin "1") (pinfunction "K_1") (pintype "unspecified"))
      (node (ref "Q1") (pin "1") (pinfunction "G_1") (pintype "unspecified"))
      (node (ref "R25") (pin "1") (pinfunction "1_1") (pintype "input"))
    )
    (net (code "54") (name "Net-(LED1-A)") (class "Default")
      (node (ref "LED1") (pin "2") (pinfunction "A_2") (pintype "input"))
      (node (ref "R1") (pin "2") (pinfunction "2_2") (pintype "input"))
    )
    (net (code "55") (name "Net-(LED4-A)") (class "Default")
      (node (ref "LED4") (pin "2") (pinfunction "A_2") (pintype "input"))
      (node (ref "R20") (pin "2") (pinfunction "2_2") (pintype "input"))
    )
    (net (code "56") (name "Net-(LED5-A)") (class "Default")
      (node (ref "LED5") (pin "2") (pinfunction "A_2") (pintype "input"))
      (node (ref "R24") (pin "2") (pinfunction "2_2") (pintype "input"))
    )
    (net (code "57") (name "Net-(LED6-A)") (class "Default")
      (node (ref "LED6") (pin "2") (pinfunction "A_2") (pintype "input"))
      (node (ref "R23") (pin "2") (pinfunction "2_2") (pintype "input"))
    )
    (net (code "58") (name "Net-(Q1-D)") (class "Default")
      (node (ref "P3") (pin "2") (pinfunction "2_2") (pintype "input"))
      (node (ref "Q1") (pin "3") (pinfunction "D_3") (pintype "unspecified"))
      (node (ref "R27") (pin "1") (pinfunction "1_1") (pintype "input"))
    )
    (net (code "59") (name "Net-(U1-CP1)") (class "Default")
      (node (ref "C2") (pin "2") (pinfunction "2_2") (pintype "input"))
      (node (ref "U1") (pin "1") (pinfunction "CP1_1") (pintype "input"))
    )
    (net (code "60") (name "Net-(U1-CP2)") (class "Default")
      (node (ref "C2") (pin "1") (pinfunction "1_1") (pintype "input"))
      (node (ref "U1") (pin "2") (pinfunction "CP2_2") (pintype "input"))
    )
    (net (code "61") (name "Net-(U1-FAULT#)") (class "Default")
      (node (ref "R1") (pin "1") (pinfunction "1_1") (pintype "input"))
      (node (ref "U1") (pin "18") (pinfunction "FAULT#_18") (pintype "input"))
    )
    (net (code "62") (name "Net-(U1-RESET#)") (class "Default")
      (node (ref "C4") (pin "2") (pinfunction "2_2") (pintype "input"))
      (node (ref "U1") (pin "15") (pinfunction "V3P3OUT_15") (pintype "input"))
      (node (ref "U1") (pin "16") (pinfunction "RESET#_16") (pintype "input"))
      (node (ref "U1") (pin "17") (pinfunction "SLEEP#_17") (pintype "input"))
    )
    (net (code "63") (name "Net-(U1-VCP)") (class "Default")
      (node (ref "C3") (pin "2") (pinfunction "2_2") (pintype "input"))
      (node (ref "U1") (pin "3") (pinfunction "VCP_3") (pintype "input"))
    )
    (net (code "64") (name "Net-(U11-BOOT)") (class "Default")
      (node (ref "C29") (pin "1") (pinfunction "1_1") (pintype "input"))
      (node (ref "U11") (pin "1") (pinfunction "BOOT_1") (pintype "unspecified"))
    )
    (net (code "65") (name "Net-(U11-VSNS)") (class "Default")
      (node (ref "R21") (pin "1") (pinfunction "1_1") (pintype "input"))
      (node (ref "R22") (pin "2") (pinfunction "2_2") (pintype "input"))
      (node (ref "U11") (pin "4") (pinfunction "VSNS_4") (pintype "unspecified"))
    )
    (net (code "66") (name "PGND") (class "Default")
      (node (ref "C1") (pin "1") (pinfunction "1_1") (pintype "input"))
      (node (ref "C35") (pin "2") (pinfunction "2_2") (pintype "input"))
      (node (ref "C36") (pin "1") (pinfunction "1_1") (pintype "input"))
      (node (ref "C38") (pin "2") (pinfunction "2_2") (pintype "input"))
      (node (ref "C4") (pin "1") (pinfunction "1_1") (pintype "input"))
      (node (ref "D3") (pin "2") (pinfunction "A_2") (pintype "unspecified"))
      (node (ref "LED1") (pin "1") (pinfunction "C_1") (pintype "input"))
      (node (ref "LED6") (pin "1") (pinfunction "C_1") (pintype "input"))
      (node (ref "Q1") (pin "2") (pinfunction "S_2") (pintype "unspecified"))
      (node (ref "R2") (pin "1") (pinfunction "1_1") (pintype "unspecified"))
      (node (ref "R27") (pin "2") (pinfunction "2_2") (pintype "input"))
      (node (ref "U1") (pin "10") (pinfunction "PGND3_10") (pintype "input"))
      (node (ref "U1") (pin "12") (pinfunction "COMPP_12") (pintype "input"))
      (node (ref "U1") (pin "13") (pinfunction "COMPN_13") (pintype "input"))
      (node (ref "U1") (pin "14") (pinfunction "GND_14") (pintype "input"))
      (node (ref "U1") (pin "19") (pinfunction "COMPO#_19") (pintype "input"))
      (node (ref "U1") (pin "20") (pinfunction "GND_20") (pintype "input"))
      (node (ref "U1") (pin "21") (pinfunction "NC_21") (pintype "input"))
      (node (ref "U1") (pin "28") (pinfunction "GND_28") (pintype "input"))
      (node (ref "U1") (pin "29") (pinfunction "EP_29") (pintype "input"))
      (node (ref "U1") (pin "6") (pinfunction "PGND1_6") (pintype "input"))
      (node (ref "U1") (pin "7") (pinfunction "PGND2_7") (pintype "input"))
    )
    (net (code "67") (name "VCC-3.3V") (class "Default")
      (node (ref "C26") (pin "1") (pinfunction "1_1") (pintype "unspecified"))
      (node (ref "C28") (pin "2") (pinfunction "2_2") (pintype "unspecified"))
      (node (ref "H12") (pin "2") (pinfunction "2_2") (pintype "unspecified"))
      (node (ref "R20") (pin "1") (pinfunction "1_1") (pintype "input"))
      (node (ref "U10") (pin "2") (pinfunction "Vout_2") (pintype "unspecified"))
      (node (ref "U10") (pin "4") (pinfunction "Vout_4") (pintype "unspecified"))
      (node (ref "U12") (pin "4") (pinfunction "4_4") (pintype "unspecified"))
      (node (ref "U13") (pin "4") (pinfunction "4_4") (pintype "unspecified"))
      (node (ref "U6") (pin "5") (pinfunction "VS_5") (pintype "unspecified"))
      (node (ref "U6") (pin "6") (pinfunction "REF2_6") (pintype "unspecified"))
      (node (ref "U7") (pin "5") (pinfunction "VS_5") (pintype "unspecified"))
      (node (ref "U7") (pin "6") (pinfunction "REF2_6") (pintype "unspecified"))
    )
    (net (code "68") (name "VCC-5V") (class "Default")
      (node (ref "C24") (pin "1") (pinfunction "1_1") (pintype "unspecified"))
      (node (ref "C27") (pin "2") (pinfunction "2_2") (pintype "unspecified"))
      (node (ref "C32") (pin "1") (pinfunction "1_1") (pintype "input"))
      (node (ref "C37") (pin "1") (pinfunction "1_1") (pintype "input"))
      (node (ref "H10") (pin "3") (pinfunction "3_3") (pintype "input"))
      (node (ref "H14") (pin "3") (pinfunction "3_3") (pintype "input"))
      (node (ref "L1") (pin "2") (pinfunction "2_2") (pintype "unspecified"))
      (node (ref "R21") (pin "2") (pinfunction "2_2") (pintype "input"))
      (node (ref "R24") (pin "1") (pinfunction "1_1") (pintype "input"))
      (node (ref "U10") (pin "3") (pinfunction "Vin_3") (pintype "unspecified"))
    )
    (net (code "69") (name "VIN") (class "Default")
      (node (ref "C1") (pin "2") (pinfunction "2_2") (pintype "input"))
      (node (ref "C3") (pin "1") (pinfunction "1_1") (pintype "input"))
      (node (ref "C33") (pin "1") (pinfunction "1_1") (pintype "input"))
      (node (ref "C34") (pin "1") (pinfunction "1_1") (pintype "input"))
      (node (ref "C38") (pin "1") (pinfunction "1_1") (pintype "input"))
      (node (ref "R23") (pin "1") (pinfunction "1_1") (pintype "input"))
      (node (ref "SW1") (pin "2") (pinfunction "2_2") (pintype "unspecified"))
      (node (ref "U1") (pin "11") (pinfunction "VM_11") (pintype "input"))
      (node (ref "U1") (pin "4") (pinfunction "VM_4") (pintype "input"))
      (node (ref "U11") (pin "7") (pinfunction "VIN_7") (pintype "unspecified"))
    )
    (net (code "70") (name "VIN_12V") (class "Default")
      (node (ref "C35") (pin "1") (pinfunction "1_1") (pintype "input"))
      (node (ref "P3") (pin "1") (pinfunction "1_1") (pintype "input"))
      (node (ref "R25") (pin "2") (pinfunction "2_2") (pintype "input"))
      (node (ref "SW1") (pin "3") (pinfunction "3_3") (pintype "unspecified"))
    )
    (net (code "71") (name "unconnected-(SW1-Pad1)") (class "Default")
      (node (ref "SW1") (pin "1") (pinfunction "1_1") (pintype "unspecified+no_connect"))
    )
    (net (code "72") (name "unconnected-(U6-NC-Pad1)") (class "Default")
      (node (ref "U6") (pin "1") (pinfunction "NC_1") (pintype "unspecified+no_connect"))
    )
    (net (code "73") (name "unconnected-(U7-NC-Pad1)") (class "Default")
      (node (ref "U7") (pin "1") (pinfunction "NC_1") (pintype "unspecified+no_connect"))
    )
    (net (code "74") (name "unconnected-(U11-ENA-Pad5)") (class "Default")
      (node (ref "U11") (pin "5") (pinfunction "ENA_5") (pintype "unspecified+no_connect"))
    )
    (net (code "75") (name "unconnected-(U11-NC-Pad2)") (class "Default")
      (node (ref "U11") (pin "2") (pinfunction "NC_2") (pintype "unspecified+no_connect"))
    )
    (net (code "76") (name "unconnected-(U11-NC-Pad3)") (class "Default")
      (node (ref "U11") (pin "3") (pinfunction "NC_3") (pintype "unspecified+no_connect"))
    )
    (net (code "77") (name "unconnected-(U12-Pad5)") (class "Default")
      (node (ref "U12") (pin "5") (pinfunction "5_5") (pintype "unspecified+no_connect"))
    )
    (net (code "78") (name "unconnected-(U12-Pad6)") (class "Default")
      (node (ref "U12") (pin "6") (pinfunction "6_6") (pintype "unspecified+no_connect"))
    )
    (net (code "79") (name "unconnected-(U13-Pad5)") (class "Default")
      (node (ref "U13") (pin "5") (pinfunction "5_5") (pintype "unspecified+no_connect"))
    )
    (net (code "80") (name "unconnected-(U13-Pad6)") (class "Default")
      (node (ref "U13") (pin "6") (pinfunction "6_6") (pintype "unspecified+no_connect"))
    )
  )
)
